# Lighting_Schematic.net
KiCad netlist of a schematic drawn in EAGLE
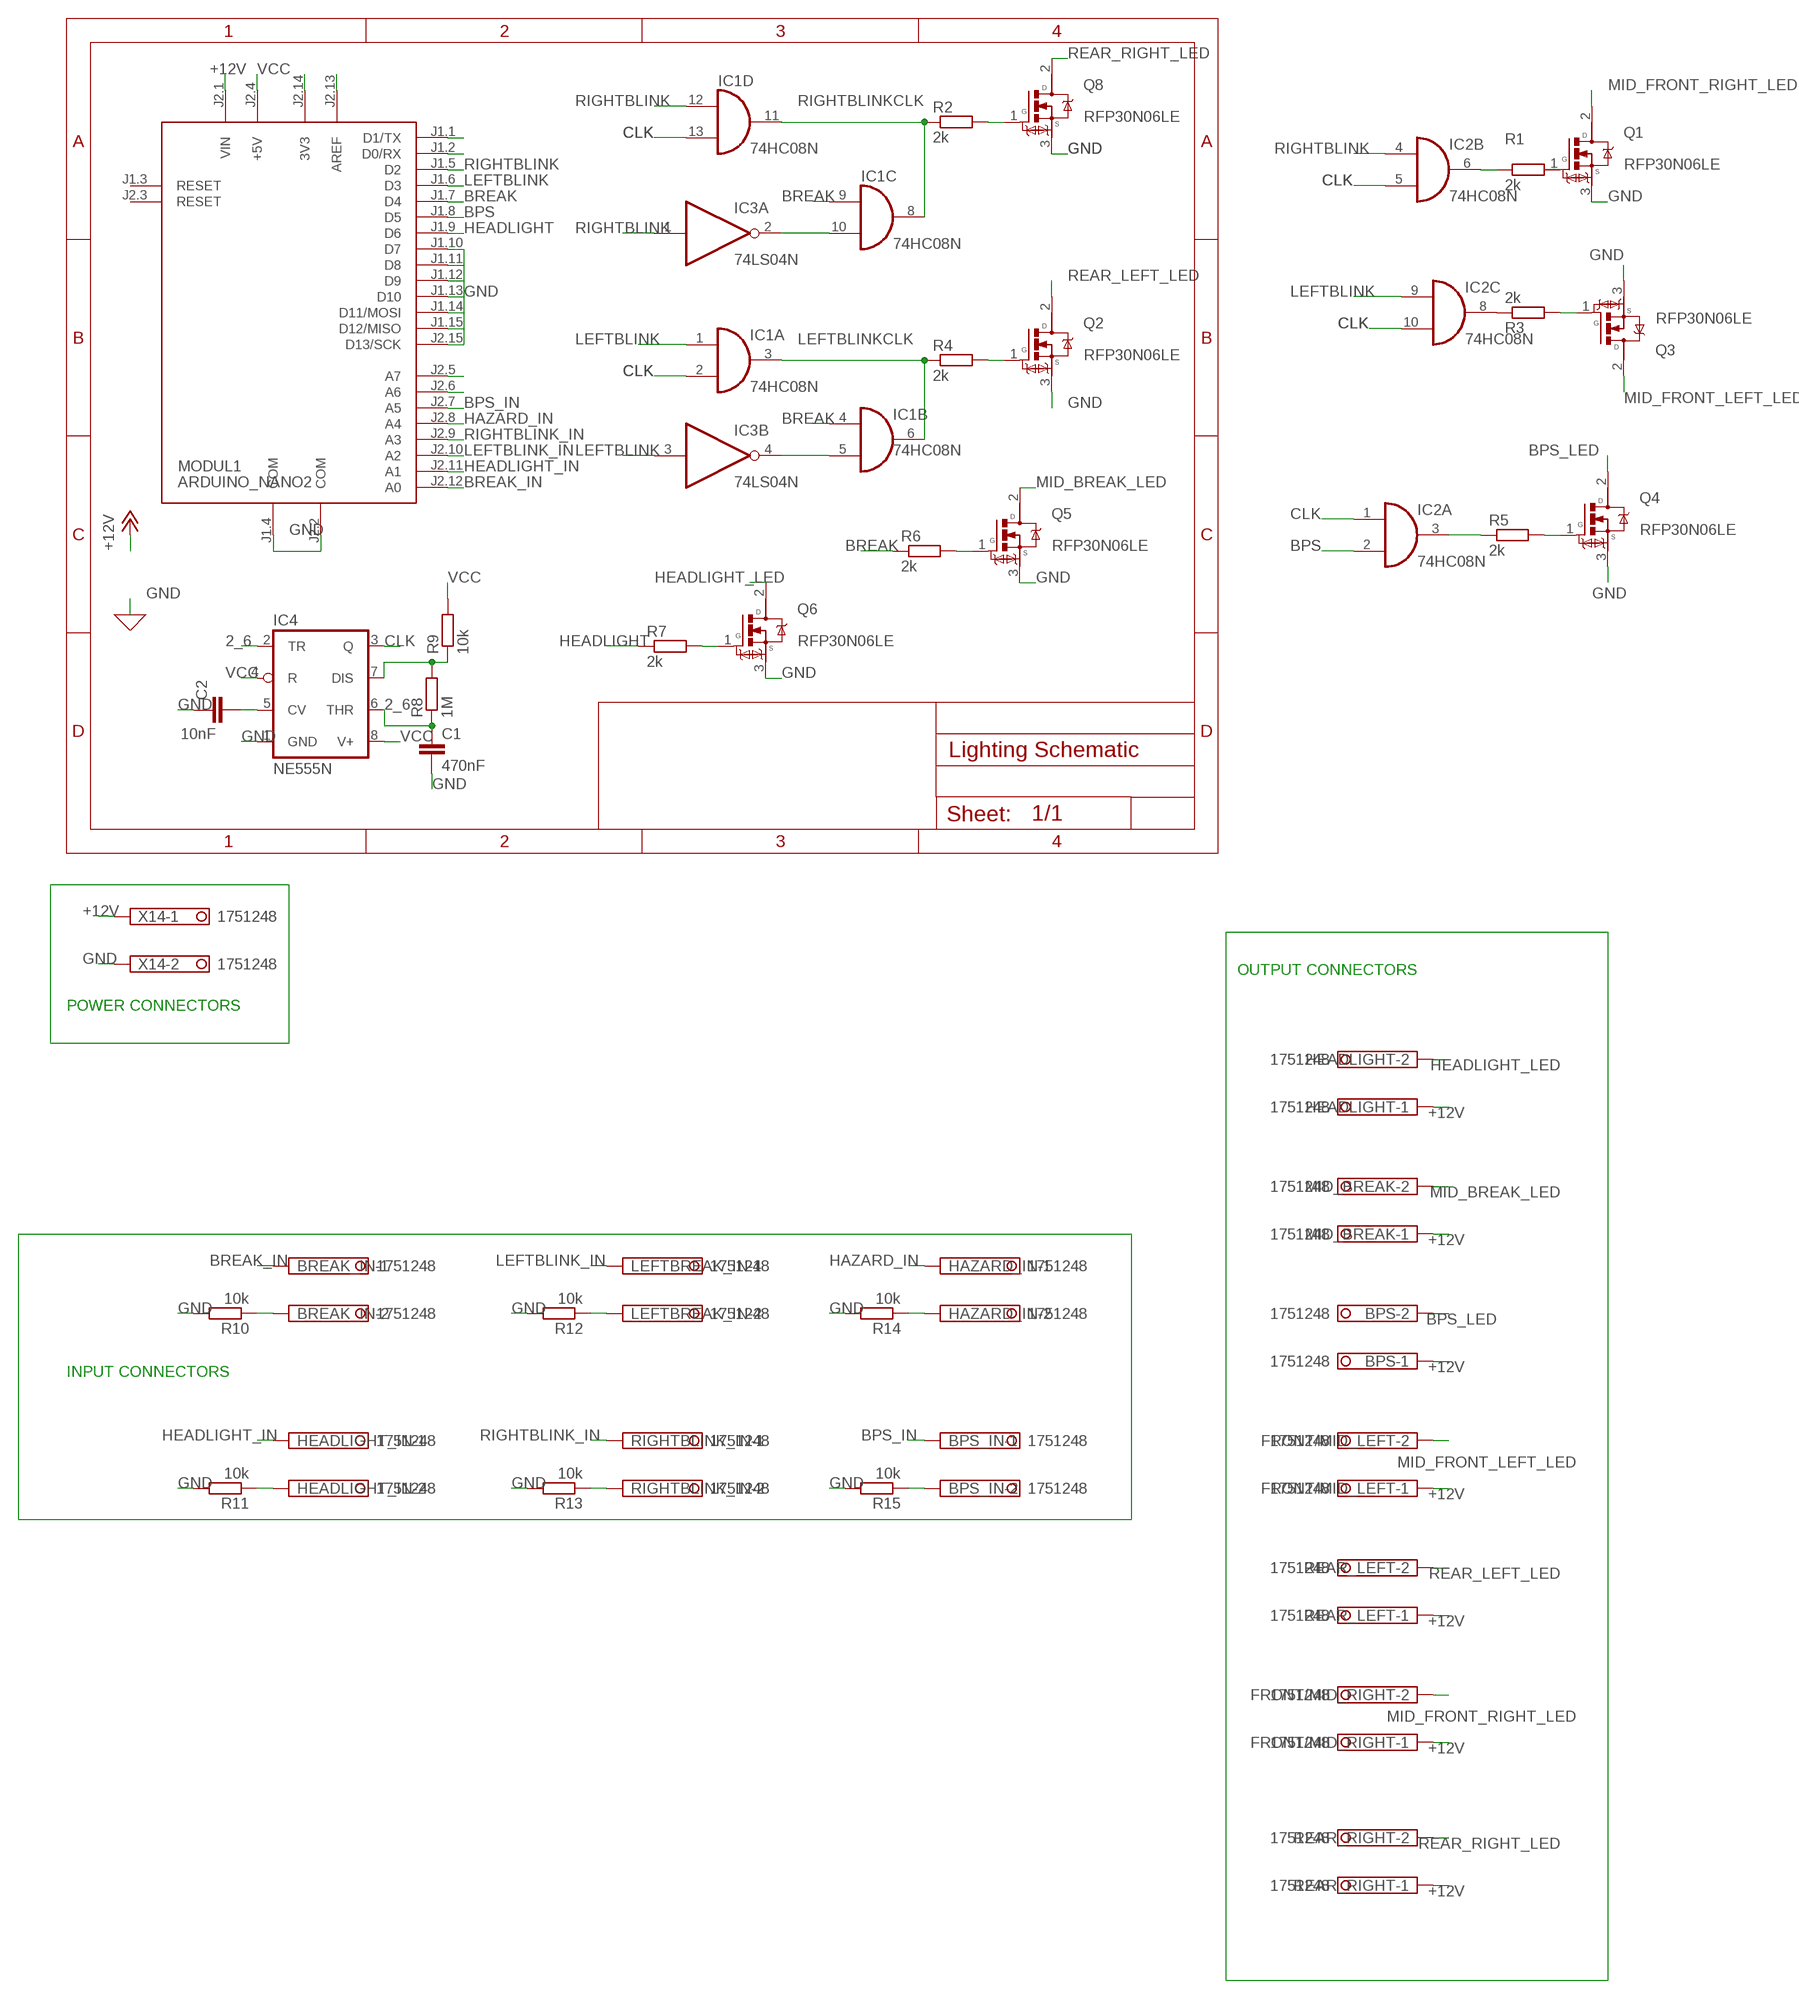
[diagram p0: schematic, sheet 1]

(export (version "E")
  (design (tool "Eeschema 10.0.6"))
  (components
    (comp (ref "BPS")
      (value "1751248")
      (footprint "eagle-import:1751248")
      (libsource (lib "eagle-import") (part "1751248"))
    )
    (comp (ref "BPS_IN")
      (value "1751248")
      (footprint "eagle-import:1751248")
      (libsource (lib "eagle-import") (part "1751248"))
    )
    (comp (ref "BREAK_IN")
      (value "1751248")
      (footprint "eagle-import:1751248")
      (libsource (lib "eagle-import") (part "1751248"))
    )
    (comp (ref "C1")
      (value "470nF")
      (footprint "eagle-import:C2.5-2")
      (libsource (lib "eagle-import") (part "C2.5/2"))
    )
    (comp (ref "C2")
      (value "10nF")
      (footprint "eagle-import:C2.5-2")
      (libsource (lib "eagle-import") (part "C2.5/2"))
    )
    (comp (ref "FRONT/MID_LEFT")
      (value "1751248")
      (footprint "eagle-import:1751248")
      (libsource (lib "eagle-import") (part "1751248"))
    )
    (comp (ref "FRONT/MID_RIGHT")
      (value "1751248")
      (footprint "eagle-import:1751248")
      (libsource (lib "eagle-import") (part "1751248"))
    )
    (comp (ref "HAZARD_IN")
      (value "1751248")
      (footprint "eagle-import:1751248")
      (libsource (lib "eagle-import") (part "1751248"))
    )
    (comp (ref "HEADLIGHT")
      (value "1751248")
      (footprint "eagle-import:1751248")
      (libsource (lib "eagle-import") (part "1751248"))
    )
    (comp (ref "HEADLIGHT_IN")
      (value "1751248")
      (footprint "eagle-import:1751248")
      (libsource (lib "eagle-import") (part "1751248"))
    )
    (comp (ref "IC1")
      (value "74HC08N")
      (footprint "eagle-import:DIL14")
      (libsource (lib "eagle-import") (part "7408NHC"))
    )
    (comp (ref "IC2")
      (value "74HC08N")
      (footprint "eagle-import:DIL14")
      (libsource (lib "eagle-import") (part "7408NHC"))
    )
    (comp (ref "IC3")
      (value "74LS04N")
      (footprint "eagle-import:DIL14")
      (libsource (lib "eagle-import") (part "7404NLS"))
    )
    (comp (ref "IC4")
      (value "NE555N")
      (footprint "eagle-import:DIL08")
      (libsource (lib "eagle-import") (part "555NNE"))
    )
    (comp (ref "LEFTBREAK_IN")
      (value "1751248")
      (footprint "eagle-import:1751248")
      (libsource (lib "eagle-import") (part "1751248"))
    )
    (comp (ref "MID_BREAK")
      (value "1751248")
      (footprint "eagle-import:1751248")
      (libsource (lib "eagle-import") (part "1751248"))
    )
    (comp (ref "MODUL1")
      (value "ARDUINO_NANO2")
      (footprint "eagle-import:ARDUINO_NANO2")
      (libsource (lib "eagle-import") (part "ARDUINO_NANO2"))
    )
    (comp (ref "Q1")
      (value "RFP30N06LE")
      (footprint "eagle-import:TRANS_RFP30N06LE")
      (fields (field (name "MF") "ON Semiconductor"))
      (libsource (lib "eagle-import") (part "RFP30N06LE"))
    )
    (comp (ref "Q2")
      (value "RFP30N06LE")
      (footprint "eagle-import:TRANS_RFP30N06LE")
      (fields (field (name "MF") "ON Semiconductor"))
      (libsource (lib "eagle-import") (part "RFP30N06LE"))
    )
    (comp (ref "Q3")
      (value "RFP30N06LE")
      (footprint "eagle-import:TRANS_RFP30N06LE")
      (fields (field (name "MF") "ON Semiconductor"))
      (libsource (lib "eagle-import") (part "RFP30N06LE"))
    )
    (comp (ref "Q4")
      (value "RFP30N06LE")
      (footprint "eagle-import:TRANS_RFP30N06LE")
      (fields (field (name "MF") "ON Semiconductor"))
      (libsource (lib "eagle-import") (part "RFP30N06LE"))
    )
    (comp (ref "Q5")
      (value "RFP30N06LE")
      (footprint "eagle-import:TRANS_RFP30N06LE")
      (fields (field (name "MF") "ON Semiconductor"))
      (libsource (lib "eagle-import") (part "RFP30N06LE"))
    )
    (comp (ref "Q6")
      (value "RFP30N06LE")
      (footprint "eagle-import:TRANS_RFP30N06LE")
      (fields (field (name "MF") "ON Semiconductor"))
      (libsource (lib "eagle-import") (part "RFP30N06LE"))
    )
    (comp (ref "Q8")
      (value "RFP30N06LE")
      (footprint "eagle-import:TRANS_RFP30N06LE")
      (fields (field (name "MF") "ON Semiconductor"))
      (libsource (lib "eagle-import") (part "RFP30N06LE"))
    )
    (comp (ref "R1")
      (value "2k")
      (footprint "eagle-import:0204_5")
      (libsource (lib "eagle-import") (part "R-EU_0204/5"))
    )
    (comp (ref "R2")
      (value "2k")
      (footprint "eagle-import:0204_5")
      (libsource (lib "eagle-import") (part "R-EU_0204/5"))
    )
    (comp (ref "R3")
      (value "2k")
      (footprint "eagle-import:0204_5")
      (libsource (lib "eagle-import") (part "R-EU_0204/5"))
    )
    (comp (ref "R4")
      (value "2k")
      (footprint "eagle-import:0204_5")
      (libsource (lib "eagle-import") (part "R-EU_0204/5"))
    )
    (comp (ref "R5")
      (value "2k")
      (footprint "eagle-import:0204_5")
      (libsource (lib "eagle-import") (part "R-EU_0204/5"))
    )
    (comp (ref "R6")
      (value "2k")
      (footprint "eagle-import:0204_5")
      (libsource (lib "eagle-import") (part "R-EU_0204/5"))
    )
    (comp (ref "R7")
      (value "2k")
      (footprint "eagle-import:0204_5")
      (libsource (lib "eagle-import") (part "R-EU_0204/5"))
    )
    (comp (ref "R8")
      (value "1M")
      (footprint "eagle-import:0204_5")
      (libsource (lib "eagle-import") (part "R-EU_0204/5"))
    )
    (comp (ref "R9")
      (value "10k")
      (footprint "eagle-import:0204_5")
      (libsource (lib "eagle-import") (part "R-EU_0204/5"))
    )
    (comp (ref "R10")
      (value "10k")
      (footprint "eagle-import:0204_5")
      (libsource (lib "eagle-import") (part "R-EU_0204/5"))
    )
    (comp (ref "R11")
      (value "10k")
      (footprint "eagle-import:0204_5")
      (libsource (lib "eagle-import") (part "R-EU_0204/5"))
    )
    (comp (ref "R12")
      (value "10k")
      (footprint "eagle-import:0204_5")
      (libsource (lib "eagle-import") (part "R-EU_0204/5"))
    )
    (comp (ref "R13")
      (value "10k")
      (footprint "eagle-import:0204_5")
      (libsource (lib "eagle-import") (part "R-EU_0204/5"))
    )
    (comp (ref "R14")
      (value "10k")
      (footprint "eagle-import:0204_5")
      (libsource (lib "eagle-import") (part "R-EU_0204/5"))
    )
    (comp (ref "R15")
      (value "10k")
      (footprint "eagle-import:0204_5")
      (libsource (lib "eagle-import") (part "R-EU_0204/5"))
    )
    (comp (ref "REAR_LEFT")
      (value "1751248")
      (footprint "eagle-import:1751248")
      (libsource (lib "eagle-import") (part "1751248"))
    )
    (comp (ref "REAR_RIGHT")
      (value "1751248")
      (footprint "eagle-import:1751248")
      (libsource (lib "eagle-import") (part "1751248"))
    )
    (comp (ref "RIGHTBLINK_IN")
      (value "1751248")
      (footprint "eagle-import:1751248")
      (libsource (lib "eagle-import") (part "1751248"))
    )
    (comp (ref "X14")
      (value "1751248")
      (footprint "eagle-import:1751248")
      (libsource (lib "eagle-import") (part "1751248"))
    )
  )
  (nets
    (net (code "1") (name "+12V") (class "Default")
      (node (ref "BPS") (pin "1") (pinfunction "K_1") (pintype "passive"))
      (node (ref "FRONT/MID_LEFT") (pin "1") (pinfunction "K_1") (pintype "passive"))
      (node (ref "FRONT/MID_RIGHT") (pin "1") (pinfunction "K_1") (pintype "passive"))
      (node (ref "HEADLIGHT") (pin "1") (pinfunction "K_1") (pintype "passive"))
      (node (ref "MID_BREAK") (pin "1") (pinfunction "K_1") (pintype "passive"))
      (node (ref "MODUL1") (pin "J2.1") (pinfunction "VIN_J2.1") (pintype "power_in"))
      (node (ref "REAR_LEFT") (pin "1") (pinfunction "K_1") (pintype "passive"))
      (node (ref "REAR_RIGHT") (pin "1") (pinfunction "K_1") (pintype "passive"))
      (node (ref "X14") (pin "1") (pinfunction "K_1") (pintype "passive"))
    )
    (net (code "2") (name "/2_6") (class "Default")
      (node (ref "C1") (pin "1") (pinfunction "1_1") (pintype "passive"))
      (node (ref "IC4") (pin "2") (pinfunction "TR_2") (pintype "input"))
      (node (ref "IC4") (pin "6") (pinfunction "THR_6") (pintype "input"))
      (node (ref "R8") (pin "1") (pinfunction "1_1") (pintype "passive"))
    )
    (net (code "3") (name "/BPS") (class "Default")
      (node (ref "IC2") (pin "2") (pinfunction "I1_2") (pintype "input"))
      (node (ref "MODUL1") (pin "J1.8") (pinfunction "D5_J1.8") (pintype "bidirectional"))
    )
    (net (code "4") (name "/BPS_IN") (class "Default")
      (node (ref "BPS_IN") (pin "1") (pinfunction "K_1") (pintype "passive"))
      (node (ref "MODUL1") (pin "J2.7") (pinfunction "A5_J2.7") (pintype "bidirectional"))
    )
    (net (code "5") (name "/BPS_LED") (class "Default")
      (node (ref "BPS") (pin "2") (pinfunction "K_2") (pintype "passive"))
      (node (ref "Q4") (pin "2") (pinfunction "D_2") (pintype "power_in"))
    )
    (net (code "6") (name "/BREAK") (class "Default")
      (node (ref "IC1") (pin "4") (pinfunction "I0_4") (pintype "input"))
      (node (ref "IC1") (pin "9") (pinfunction "I0_9") (pintype "input"))
      (node (ref "MODUL1") (pin "J1.7") (pinfunction "D4_J1.7") (pintype "bidirectional"))
      (node (ref "R6") (pin "1") (pinfunction "1_1") (pintype "passive"))
    )
    (net (code "7") (name "/BREAK_IN") (class "Default")
      (node (ref "BREAK_IN") (pin "1") (pinfunction "K_1") (pintype "passive"))
      (node (ref "MODUL1") (pin "J2.12") (pinfunction "A0_J2.12") (pintype "bidirectional"))
    )
    (net (code "8") (name "/CLK") (class "Default")
      (node (ref "IC1") (pin "13") (pinfunction "I1_13") (pintype "input"))
      (node (ref "IC1") (pin "2") (pinfunction "I1_2") (pintype "input"))
      (node (ref "IC2") (pin "1") (pinfunction "I0_1") (pintype "input"))
      (node (ref "IC2") (pin "10") (pinfunction "I1_10") (pintype "input"))
      (node (ref "IC2") (pin "5") (pinfunction "I1_5") (pintype "input"))
      (node (ref "IC4") (pin "3") (pinfunction "Q_3") (pintype "output"))
    )
    (net (code "9") (name "/HAZARD_IN") (class "Default")
      (node (ref "HAZARD_IN") (pin "1") (pinfunction "K_1") (pintype "passive"))
      (node (ref "MODUL1") (pin "J2.8") (pinfunction "A4_J2.8") (pintype "bidirectional"))
    )
    (net (code "10") (name "/HEADLIGHT") (class "Default")
      (node (ref "MODUL1") (pin "J1.9") (pinfunction "D6_J1.9") (pintype "bidirectional"))
      (node (ref "R7") (pin "1") (pinfunction "1_1") (pintype "passive"))
    )
    (net (code "11") (name "/HEADLIGHT_IN") (class "Default")
      (node (ref "HEADLIGHT_IN") (pin "1") (pinfunction "K_1") (pintype "passive"))
      (node (ref "MODUL1") (pin "J2.11") (pinfunction "A1_J2.11") (pintype "bidirectional"))
    )
    (net (code "12") (name "/HEADLIGHT_LED") (class "Default")
      (node (ref "HEADLIGHT") (pin "2") (pinfunction "K_2") (pintype "passive"))
      (node (ref "Q6") (pin "2") (pinfunction "D_2") (pintype "power_in"))
    )
    (net (code "13") (name "/LEFTBLINK") (class "Default")
      (node (ref "IC1") (pin "1") (pinfunction "I0_1") (pintype "input"))
      (node (ref "IC2") (pin "9") (pinfunction "I0_9") (pintype "input"))
      (node (ref "IC3") (pin "3") (pinfunction "I_3") (pintype "input"))
      (node (ref "MODUL1") (pin "J1.6") (pinfunction "D3_J1.6") (pintype "bidirectional"))
    )
    (net (code "14") (name "/LEFTBLINKCLK") (class "Default")
      (node (ref "IC1") (pin "3") (pinfunction "O_3") (pintype "output"))
      (node (ref "IC1") (pin "6") (pinfunction "O_6") (pintype "output"))
      (node (ref "R4") (pin "1") (pinfunction "1_1") (pintype "passive"))
    )
    (net (code "15") (name "/LEFTBLINK_IN") (class "Default")
      (node (ref "LEFTBREAK_IN") (pin "1") (pinfunction "K_1") (pintype "passive"))
      (node (ref "MODUL1") (pin "J2.10") (pinfunction "A2_J2.10") (pintype "bidirectional"))
    )
    (net (code "16") (name "/MID_BREAK_LED") (class "Default")
      (node (ref "MID_BREAK") (pin "2") (pinfunction "K_2") (pintype "passive"))
      (node (ref "Q5") (pin "2") (pinfunction "D_2") (pintype "power_in"))
    )
    (net (code "17") (name "/MID_FRONT_LEFT_LED") (class "Default")
      (node (ref "FRONT/MID_LEFT") (pin "2") (pinfunction "K_2") (pintype "passive"))
      (node (ref "Q3") (pin "2") (pinfunction "D_2") (pintype "power_in"))
    )
    (net (code "18") (name "/MID_FRONT_RIGHT_LED") (class "Default")
      (node (ref "FRONT/MID_RIGHT") (pin "2") (pinfunction "K_2") (pintype "passive"))
      (node (ref "Q1") (pin "2") (pinfunction "D_2") (pintype "power_in"))
    )
    (net (code "19") (name "/REAR_LEFT_LED") (class "Default")
      (node (ref "Q2") (pin "2") (pinfunction "D_2") (pintype "power_in"))
      (node (ref "REAR_LEFT") (pin "2") (pinfunction "K_2") (pintype "passive"))
    )
    (net (code "20") (name "/REAR_RIGHT_LED") (class "Default")
      (node (ref "Q8") (pin "2") (pinfunction "D_2") (pintype "power_in"))
      (node (ref "REAR_RIGHT") (pin "2") (pinfunction "K_2") (pintype "passive"))
    )
    (net (code "21") (name "/RIGHTBLINK") (class "Default")
      (node (ref "IC1") (pin "12") (pinfunction "I0_12") (pintype "input"))
      (node (ref "IC2") (pin "4") (pinfunction "I0_4") (pintype "input"))
      (node (ref "IC3") (pin "1") (pinfunction "I_1") (pintype "input"))
      (node (ref "MODUL1") (pin "J1.5") (pinfunction "D2_J1.5") (pintype "bidirectional"))
    )
    (net (code "22") (name "/RIGHTBLINKCLK") (class "Default")
      (node (ref "IC1") (pin "11") (pinfunction "O_11") (pintype "output"))
      (node (ref "IC1") (pin "8") (pinfunction "O_8") (pintype "output"))
      (node (ref "R2") (pin "1") (pinfunction "1_1") (pintype "passive"))
    )
    (net (code "23") (name "/RIGHTBLINK_IN") (class "Default")
      (node (ref "MODUL1") (pin "J2.9") (pinfunction "A3_J2.9") (pintype "bidirectional"))
      (node (ref "RIGHTBLINK_IN") (pin "1") (pinfunction "K_1") (pintype "passive"))
    )
    (net (code "24") (name "/VCC") (class "Default")
      (node (ref "IC4") (pin "4") (pinfunction "R_4") (pintype "input"))
      (node (ref "IC4") (pin "8") (pinfunction "V+_8") (pintype "power_in"))
      (node (ref "MODUL1") (pin "J2.4") (pinfunction "+5V_J2.4") (pintype "power_in"))
      (node (ref "R9") (pin "2") (pinfunction "2_2") (pintype "passive"))
    )
    (net (code "25") (name "GND") (class "Default")
      (node (ref "C1") (pin "2") (pinfunction "2_2") (pintype "passive"))
      (node (ref "C2") (pin "1") (pinfunction "1_1") (pintype "passive"))
      (node (ref "IC4") (pin "1") (pinfunction "GND_1") (pintype "power_in"))
      (node (ref "MODUL1") (pin "J1.10") (pinfunction "D7_J1.10") (pintype "bidirectional"))
      (node (ref "MODUL1") (pin "J1.4") (pinfunction "COM_J1.4") (pintype "power_in"))
      (node (ref "MODUL1") (pin "J2.15") (pinfunction "D13/SCK_J2.15") (pintype "bidirectional"))
      (node (ref "MODUL1") (pin "J2.2") (pinfunction "COM_J2.2") (pintype "power_in"))
      (node (ref "Q1") (pin "3") (pinfunction "S_3") (pintype "power_in"))
      (node (ref "Q2") (pin "3") (pinfunction "S_3") (pintype "power_in"))
      (node (ref "Q3") (pin "3") (pinfunction "S_3") (pintype "power_in"))
      (node (ref "Q4") (pin "3") (pinfunction "S_3") (pintype "power_in"))
      (node (ref "Q5") (pin "3") (pinfunction "S_3") (pintype "power_in"))
      (node (ref "Q6") (pin "3") (pinfunction "S_3") (pintype "power_in"))
      (node (ref "Q8") (pin "3") (pinfunction "S_3") (pintype "power_in"))
      (node (ref "R10") (pin "2") (pinfunction "2_2") (pintype "passive"))
      (node (ref "R11") (pin "2") (pinfunction "2_2") (pintype "passive"))
      (node (ref "R12") (pin "2") (pinfunction "2_2") (pintype "passive"))
      (node (ref "R13") (pin "2") (pinfunction "2_2") (pintype "passive"))
      (node (ref "R14") (pin "2") (pinfunction "2_2") (pintype "passive"))
      (node (ref "R15") (pin "2") (pinfunction "2_2") (pintype "passive"))
      (node (ref "X14") (pin "2") (pinfunction "K_2") (pintype "passive"))
    )
    (net (code "26") (name "Net-(BPS_INB-K)") (class "Default")
      (node (ref "BPS_IN") (pin "2") (pinfunction "K_2") (pintype "passive"))
      (node (ref "R15") (pin "1") (pinfunction "1_1") (pintype "passive"))
    )
    (net (code "27") (name "Net-(BREAK_INB-K)") (class "Default")
      (node (ref "BREAK_IN") (pin "2") (pinfunction "K_2") (pintype "passive"))
      (node (ref "R10") (pin "1") (pinfunction "1_1") (pintype "passive"))
    )
    (net (code "28") (name "Net-(HAZARD_INB-K)") (class "Default")
      (node (ref "HAZARD_IN") (pin "2") (pinfunction "K_2") (pintype "passive"))
      (node (ref "R14") (pin "1") (pinfunction "1_1") (pintype "passive"))
    )
    (net (code "29") (name "Net-(HEADLIGHT_INB-K)") (class "Default")
      (node (ref "HEADLIGHT_IN") (pin "2") (pinfunction "K_2") (pintype "passive"))
      (node (ref "R11") (pin "1") (pinfunction "1_1") (pintype "passive"))
    )
    (net (code "30") (name "Net-(IC1B-I1)") (class "Default")
      (node (ref "IC1") (pin "5") (pinfunction "I1_5") (pintype "input"))
      (node (ref "IC3") (pin "4") (pinfunction "O_4") (pintype "output"))
    )
    (net (code "31") (name "Net-(IC1C-I1)") (class "Default")
      (node (ref "IC1") (pin "10") (pinfunction "I1_10") (pintype "input"))
      (node (ref "IC3") (pin "2") (pinfunction "O_2") (pintype "output"))
    )
    (net (code "32") (name "Net-(IC2A-O)") (class "Default")
      (node (ref "IC2") (pin "3") (pinfunction "O_3") (pintype "output"))
      (node (ref "R5") (pin "1") (pinfunction "1_1") (pintype "passive"))
    )
    (net (code "33") (name "Net-(IC2B-O)") (class "Default")
      (node (ref "IC2") (pin "6") (pinfunction "O_6") (pintype "output"))
      (node (ref "R1") (pin "1") (pinfunction "1_1") (pintype "passive"))
    )
    (net (code "34") (name "Net-(IC2C-O)") (class "Default")
      (node (ref "IC2") (pin "8") (pinfunction "O_8") (pintype "output"))
      (node (ref "R3") (pin "1") (pinfunction "1_1") (pintype "passive"))
    )
    (net (code "35") (name "Net-(IC4-CV)") (class "Default")
      (node (ref "C2") (pin "2") (pinfunction "2_2") (pintype "passive"))
      (node (ref "IC4") (pin "5") (pinfunction "CV_5") (pintype "input"))
    )
    (net (code "36") (name "Net-(IC4-DIS)") (class "Default")
      (node (ref "IC4") (pin "7") (pinfunction "DIS_7") (pintype "input"))
      (node (ref "R8") (pin "2") (pinfunction "2_2") (pintype "passive"))
      (node (ref "R9") (pin "1") (pinfunction "1_1") (pintype "passive"))
    )
    (net (code "37") (name "Net-(LEFTBREAK_INB-K)") (class "Default")
      (node (ref "LEFTBREAK_IN") (pin "2") (pinfunction "K_2") (pintype "passive"))
      (node (ref "R12") (pin "1") (pinfunction "1_1") (pintype "passive"))
    )
    (net (code "38") (name "Net-(Q1-G)") (class "Default")
      (node (ref "Q1") (pin "1") (pinfunction "G_1") (pintype "input"))
      (node (ref "R1") (pin "2") (pinfunction "2_2") (pintype "passive"))
    )
    (net (code "39") (name "Net-(Q2-G)") (class "Default")
      (node (ref "Q2") (pin "1") (pinfunction "G_1") (pintype "input"))
      (node (ref "R4") (pin "2") (pinfunction "2_2") (pintype "passive"))
    )
    (net (code "40") (name "Net-(Q3-G)") (class "Default")
      (node (ref "Q3") (pin "1") (pinfunction "G_1") (pintype "input"))
      (node (ref "R3") (pin "2") (pinfunction "2_2") (pintype "passive"))
    )
    (net (code "41") (name "Net-(Q4-G)") (class "Default")
      (node (ref "Q4") (pin "1") (pinfunction "G_1") (pintype "input"))
      (node (ref "R5") (pin "2") (pinfunction "2_2") (pintype "passive"))
    )
    (net (code "42") (name "Net-(Q5-G)") (class "Default")
      (node (ref "Q5") (pin "1") (pinfunction "G_1") (pintype "input"))
      (node (ref "R6") (pin "2") (pinfunction "2_2") (pintype "passive"))
    )
    (net (code "43") (name "Net-(Q6-G)") (class "Default")
      (node (ref "Q6") (pin "1") (pinfunction "G_1") (pintype "input"))
      (node (ref "R7") (pin "2") (pinfunction "2_2") (pintype "passive"))
    )
    (net (code "44") (name "Net-(Q8-G)") (class "Default")
      (node (ref "Q8") (pin "1") (pinfunction "G_1") (pintype "input"))
      (node (ref "R2") (pin "2") (pinfunction "2_2") (pintype "passive"))
    )
    (net (code "45") (name "Net-(RIGHTBLINK_INB-K)") (class "Default")
      (node (ref "R13") (pin "1") (pinfunction "1_1") (pintype "passive"))
      (node (ref "RIGHTBLINK_IN") (pin "2") (pinfunction "K_2") (pintype "passive"))
    )
    (net (code "46") (name "unconnected-(MODUL1-3V3-PadJ2.14)") (class "Default")
      (node (ref "MODUL1") (pin "J2.14") (pinfunction "3V3_J2.14") (pintype "power_in"))
    )
    (net (code "47") (name "unconnected-(MODUL1-A6-PadJ2.6)") (class "Default")
      (node (ref "MODUL1") (pin "J2.6") (pinfunction "A6_J2.6") (pintype "bidirectional"))
    )
    (net (code "48") (name "unconnected-(MODUL1-A7-PadJ2.5)") (class "Default")
      (node (ref "MODUL1") (pin "J2.5") (pinfunction "A7_J2.5") (pintype "bidirectional"))
    )
    (net (code "49") (name "unconnected-(MODUL1-AREF-PadJ2.13)") (class "Default")
      (node (ref "MODUL1") (pin "J2.13") (pinfunction "AREF_J2.13") (pintype "power_in"))
    )
    (net (code "50") (name "unconnected-(MODUL1-D0{slash}RX-PadJ1.2)") (class "Default")
      (node (ref "MODUL1") (pin "J1.2") (pinfunction "D0/RX_J1.2") (pintype "bidirectional"))
    )
    (net (code "51") (name "unconnected-(MODUL1-D1{slash}TX-PadJ1.1)") (class "Default")
      (node (ref "MODUL1") (pin "J1.1") (pinfunction "D1/TX_J1.1") (pintype "bidirectional"))
    )
    (net (code "52") (name "unconnected-(MODUL1-D8-PadJ1.11)") (class "Default")
      (node (ref "MODUL1") (pin "J1.11") (pinfunction "D8_J1.11") (pintype "bidirectional"))
    )
    (net (code "53") (name "unconnected-(MODUL1-D9-PadJ1.12)") (class "Default")
      (node (ref "MODUL1") (pin "J1.12") (pinfunction "D9_J1.12") (pintype "bidirectional"))
    )
    (net (code "54") (name "unconnected-(MODUL1-D10-PadJ1.13)") (class "Default")
      (node (ref "MODUL1") (pin "J1.13") (pinfunction "D10_J1.13") (pintype "bidirectional"))
    )
    (net (code "55") (name "unconnected-(MODUL1-D11{slash}MOSI-PadJ1.14)") (class "Default")
      (node (ref "MODUL1") (pin "J1.14") (pinfunction "D11/MOSI_J1.14") (pintype "bidirectional"))
    )
    (net (code "56") (name "unconnected-(MODUL1-D12{slash}MISO-PadJ1.15)") (class "Default")
      (node (ref "MODUL1") (pin "J1.15") (pinfunction "D12/MISO_J1.15") (pintype "bidirectional"))
    )
    (net (code "57") (name "unconnected-(MODUL1-RESET-PadJ1.3)") (class "Default")
      (node (ref "MODUL1") (pin "J1.3") (pinfunction "RESET_J1.3") (pintype "bidirectional"))
    )
    (net (code "58") (name "unconnected-(MODUL1-RESET-PadJ2.3)") (class "Default")
      (node (ref "MODUL1") (pin "J2.3") (pinfunction "RESET_J2.3") (pintype "bidirectional"))
    )
  )
)
